# Zenith_Headers.net
KiCad netlist of a schematic drawn in Altium Designer
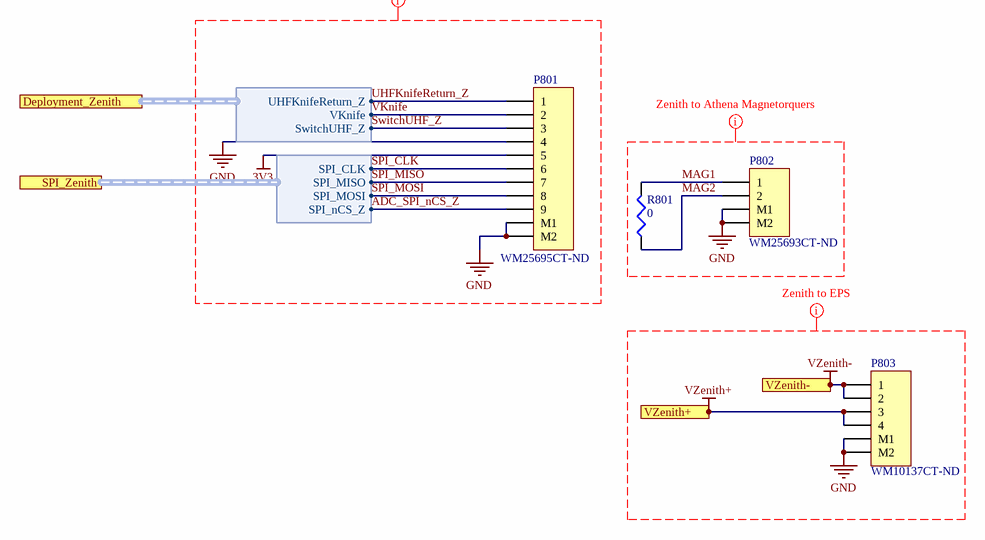
[diagram p0: Zenith_Headers.SchDoc]

(export (version "E")
  (design (tool "Eeschema 10.0.6"))
  (components
    (comp (ref "P801")
      (value "WM25695CT-ND")
      (footprint "MOLX-5040500991")
      (description "CONN HEADER SMD R/A 9POS 1.5MM")
      (fields
        (field (name "PART NUMBER") "68")
        (field (name "MANUFACTURER PART NUMBER") "5040500991")
        (field (name "PUBLISHER") "Altium Limited")
      )
      (libsource (lib "Database") (part "Header 11"))
    )
    (comp (ref "P802")
      (value "WM25693CT-ND")
      (footprint "MOLX-5040500291")
      (description "CONN HEADER SMD R/A 2POS 1.5MM")
      (fields
        (field (name "PART NUMBER") "61")
        (field (name "MANUFACTURER PART NUMBER") "5040500291")
        (field (name "PUBLISHER") "Altium Limited")
      )
      (libsource (lib "Database") (part "Header 4"))
    )
    (comp (ref "P803")
      (value "WM10137CT-ND")
      (footprint "MOLX-5040500491")
      (description "CONN HEADER SMD R/A 4POS 1.5MM")
      (fields
        (field (name "PART NUMBER") "63")
        (field (name "MANUFACTURER PART NUMBER") "5040500491")
        (field (name "PUBLISHER") "Altium Limited")
      )
      (libsource (lib "Database") (part "Header 6"))
    )
    (comp (ref "R801")
      (value "0")
      (footprint "VSH-0805MCU")
      (description "RES SMD 0.0 OHM JUMPER 1/5W 0805")
      (fields
        (field (name "PART NUMBER") "PR-VSH-00003")
        (field (name "MANUFACTURER PART NUMBER") "MCU08050Z0000ZP500")
        (field (name "PUBLISHER") "AlbertaSat")
      )
      (libsource (lib "Database") (part "Res3"))
    )
  )
  (nets
    (net (code "3") (name "/ADC_SPI_nCS_Z") (class "Default")
      (node (ref "P801") (pin "9") (pinfunction "9_9") (pintype "passive"))
    )
    (net (code "4") (name "/MAG1") (class "Default")
      (node (ref "P802") (pin "1") (pinfunction "1_1") (pintype "passive"))
      (node (ref "R801") (pin "2") (pinfunction "2_2") (pintype "passive"))
    )
    (net (code "5") (name "/MAG2") (class "Default")
      (node (ref "P802") (pin "2") (pinfunction "2_2") (pintype "passive"))
      (node (ref "R801") (pin "1") (pinfunction "1_1") (pintype "passive"))
    )
    (net (code "6") (name "/SPI_CLK") (class "Default")
      (node (ref "P801") (pin "6") (pinfunction "6_6") (pintype "passive"))
    )
    (net (code "7") (name "/SPI_MISO") (class "Default")
      (node (ref "P801") (pin "7") (pinfunction "7_7") (pintype "passive"))
    )
    (net (code "8") (name "/SPI_MOSI") (class "Default")
      (node (ref "P801") (pin "8") (pinfunction "8_8") (pintype "passive"))
    )
    (net (code "9") (name "/SwitchUHF_Z") (class "Default")
      (node (ref "P801") (pin "3") (pinfunction "3_3") (pintype "passive"))
    )
    (net (code "10") (name "/UHFKnifeReturn_Z") (class "Default")
      (node (ref "P801") (pin "1") (pinfunction "1_1") (pintype "passive"))
    )
    (net (code "11") (name "/VKnife") (class "Default")
      (node (ref "P801") (pin "2") (pinfunction "2_2") (pintype "passive"))
    )
    (net (code "14") (name "3V3") (class "Default")
      (node (ref "P801") (pin "5") (pinfunction "5_5") (pintype "passive"))
    )
    (net (code "15") (name "GND") (class "Default")
      (node (ref "P801") (pin "4") (pinfunction "4_4") (pintype "passive"))
      (node (ref "P801") (pin "M1") (pinfunction "M1_M1") (pintype "passive"))
      (node (ref "P801") (pin "M2") (pinfunction "M2_M2") (pintype "passive"))
      (node (ref "P802") (pin "M1") (pinfunction "M1_M1") (pintype "passive"))
      (node (ref "P802") (pin "M2") (pinfunction "M2_M2") (pintype "passive"))
      (node (ref "P803") (pin "M1") (pinfunction "M1_M1") (pintype "passive"))
      (node (ref "P803") (pin "M2") (pinfunction "M2_M2") (pintype "passive"))
    )
    (net (code "16") (name "VZenith+") (class "Default")
      (node (ref "P803") (pin "3") (pinfunction "3_3") (pintype "passive"))
      (node (ref "P803") (pin "4") (pinfunction "4_4") (pintype "passive"))
    )
    (net (code "17") (name "VZenith-") (class "Default")
      (node (ref "P803") (pin "1") (pinfunction "1_1") (pintype "passive"))
      (node (ref "P803") (pin "2") (pinfunction "2_2") (pintype "passive"))
    )
  )
)
